# Sheet1.net
KiCad netlist of a schematic drawn in Altium Designer
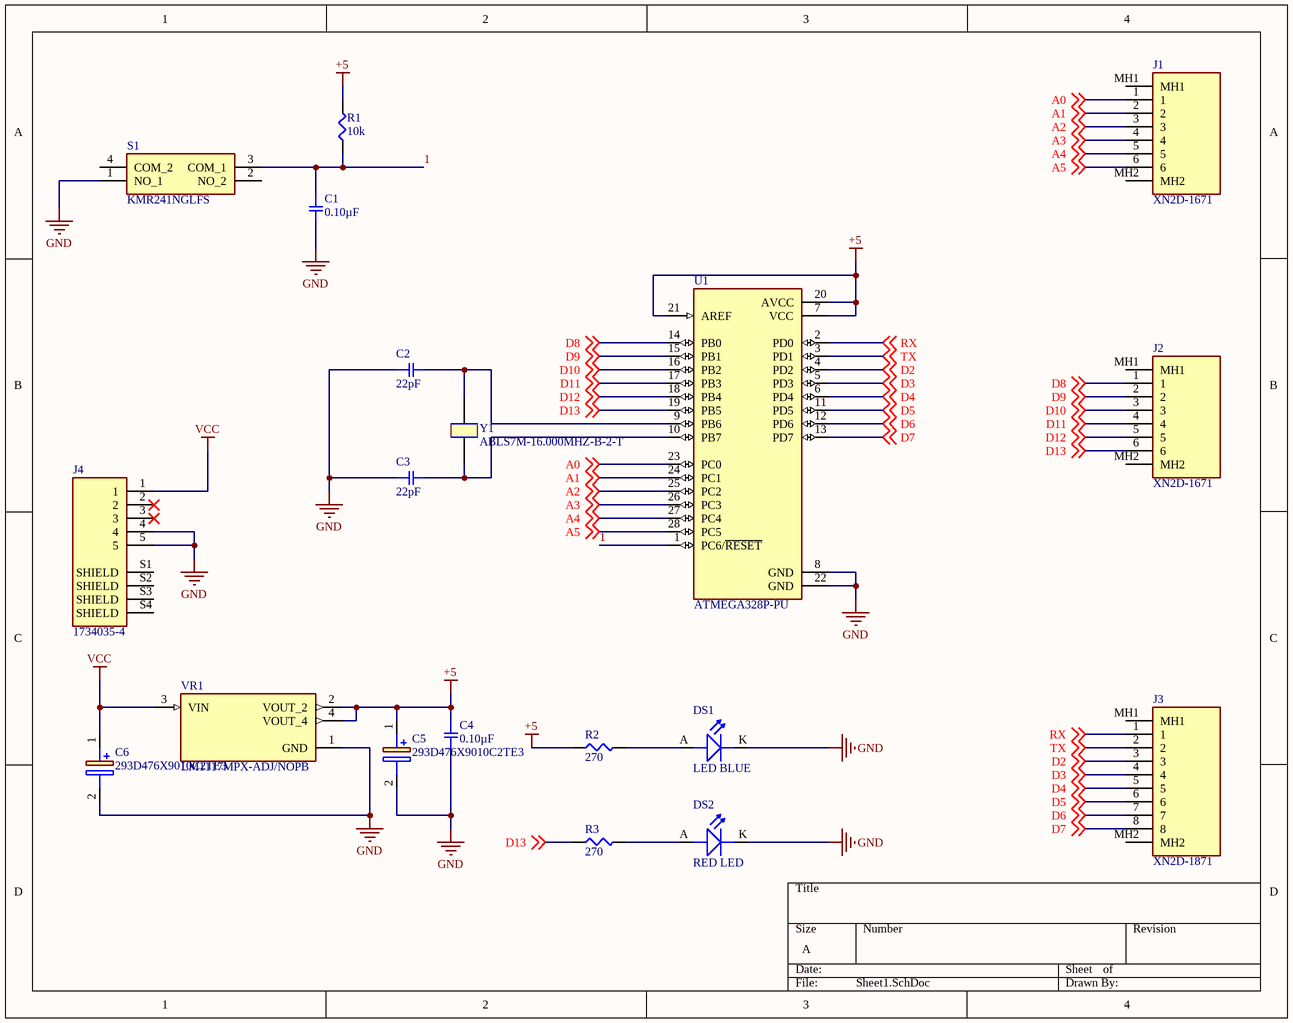
[diagram p0: Sheet1.SchDoc]

(export (version "E")
  (design (tool "Eeschema 10.0.6"))
  (components
    (comp (ref "C1")
      (value "0.10µF")
      (footprint "SMD-0402C")
      (description "CAP CER 0.1UF 16V X7R 0402")
      (fields
        (field (name "DIGI-KEY PART NUMBER") "490-4759-1-ND")
        (field (name "PART NUMBER") "GCM155R71C104KA55D")
      )
      (libsource (lib "capacitor_murata_0402") (part "GCM155R71C104KA55D"))
    )
    (comp (ref "C2")
      (value "22pF")
      (footprint "SMD-0402C")
      (description "CAP CER 22PF 25V NP0 0402")
      (fields
        (field (name "DIGI-KEY PART NUMBER") "490-8173-1-ND")
        (field (name "PART NUMBER") "GRM1555C1E220GA01D")
      )
      (libsource (lib "capacitor_murata_0402") (part "GRM1555C1E220GA01D"))
    )
    (comp (ref "C3")
      (value "22pF")
      (footprint "SMD-0402C")
      (description "CAP CER 22PF 25V NP0 0402")
      (fields
        (field (name "DIGI-KEY PART NUMBER") "490-8173-1-ND")
        (field (name "PART NUMBER") "GRM1555C1E220GA01D")
      )
      (libsource (lib "capacitor_murata_0402") (part "GRM1555C1E220GA01D"))
    )
    (comp (ref "C4")
      (value "0.10µF")
      (footprint "SMD-0402C")
      (description "CAP CER 0.1UF 16V X7R 0402")
      (fields
        (field (name "DIGI-KEY PART NUMBER") "490-4759-1-ND")
        (field (name "PART NUMBER") "GCM155R71C104KA55D")
      )
      (libsource (lib "capacitor_murata_0402") (part "GCM155R71C104KA55D"))
    )
    (comp (ref "C5")
      (value "293D476X9010C2TE3")
      (footprint "SamacSys:CAPPM6032X280N")
      (description "Capacitor Polarised")
      (fields (field (name "MOUSER PART NUMBER") "74-293D476X9010C2TE3"))
      (libsource (lib "*") (part "293D476X9010C2TE3"))
    )
    (comp (ref "C6")
      (value "293D476X9010C2TE3")
      (footprint "SamacSys:CAPPM6032X280N")
      (description "Capacitor Polarised")
      (fields (field (name "MOUSER PART NUMBER") "74-293D476X9010C2TE3"))
      (libsource (lib "*") (part "293D476X9010C2TE3"))
    )
    (comp (ref "DS1")
      (value "LED BLUE")
      (footprint "LED_0805")
      (description "Blue 470nm LED Indication - Discrete 3.3V 0805 (2012 Metric)")
      (fields
        (field (name "MANUFACTURER") "Vishay Lite-On")
        (field (name "MANUFACTURER PART NUMBER") "LTST-C171TBKT")
      )
      (libsource (lib "ESTEEMPCBLIB") (part "LED_BLUE-3V3-20mA-0805"))
    )
    (comp (ref "DS2")
      (value "RED LED")
      (footprint "LED_0805")
      (description "Red 631nm LED Indication - Discrete 2V 0805 (2012 Metric)")
      (fields
        (field (name "MANUFACTURER") "Vishay Lite-On")
        (field (name "MANUFACTURER PART NUMBER") "LTST-C171KRKT")
      )
      (libsource (lib "ESTEEMPCBLIB") (part "LED_RED-2V-20mA-0805"))
    )
    (comp (ref "J1")
      (value "XN2D-1671")
      (footprint "SamacSys:XN2D1671")
      (description "Connector")
      (fields (field (name "MOUSER PART NUMBER") "653-XN2D-1671"))
      (libsource (lib "*") (part "XN2D-1671"))
    )
    (comp (ref "J2")
      (value "XN2D-1671")
      (footprint "SamacSys:XN2D1671")
      (description "Connector")
      (fields (field (name "MOUSER PART NUMBER") "653-XN2D-1671"))
      (libsource (lib "*") (part "XN2D-1671"))
    )
    (comp (ref "J3")
      (value "XN2D-1871")
      (footprint "SamacSys:XN2D1871")
      (description "Connector")
      (libsource (lib "*") (part "XN2D-1871"))
    )
    (comp (ref "J4")
      (value "1734035-4")
      (footprint "1734035-4:J_SMD_1734035-4-5_0.8_9.9_8.85_3.9")
      (description "Conn Mini USB 2.0 Type B RCP 5 POS 0.8mm Solder RA SMD 5 Terminal 1 Port Automotive T/R")
      (fields (field (name "MF") "{'manufacturer': u'TE Connectivity'}"))
      (libsource (lib "*") (part "1734035-4"))
    )
    (comp (ref "R1")
      (value "10k")
      (footprint "SMD-0402-RES")
      (description "RES SMD 10K OHM 5% 1/10W 0402")
      (fields (field (name "PART NUMBER") "ERJ-2GEJ103X") (field (name "DIGI-KEY PART NUMBER") "P10KJCT-ND"))
      (libsource (lib "Panasonic_ERJ_0402") (part "ERJ-2GEJ103X"))
    )
    (comp (ref "R2")
      (value "270")
      (footprint "SMD-0402-RES")
      (description "RES SMD 270 OHM 1% 1/10W 0402")
      (fields (field (name "PART NUMBER") "ERJ-2RKF2700X") (field (name "DIGI-KEY PART NUMBER") "P270LCT-ND"))
      (libsource (lib "Panasonic_ERJ_0402") (part "ERJ-2RKF2700X"))
    )
    (comp (ref "R3")
      (value "270")
      (footprint "SMD-0402-RES")
      (description "RES SMD 270 OHM 1% 1/10W 0402")
      (fields (field (name "PART NUMBER") "ERJ-2RKF2700X") (field (name "DIGI-KEY PART NUMBER") "P270LCT-ND"))
      (libsource (lib "Panasonic_ERJ_0402") (part "ERJ-2RKF2700X"))
    )
    (comp (ref "S1")
      (value "KMR241NGLFS")
      (footprint "SamacSys:KMR241NGLFS")
      (description "Switch")
      (fields (field (name "MOUSER PART NUMBER") "611-KMR241NGLFS"))
      (libsource (lib "SamacSys") (part "KMR241NGLFS"))
    )
    (comp (ref "U1")
      (value "ATMEGA328P-PU")
      (footprint "ATMEGA328P-PU:DIP794W46P254L2967H457Q28B")
      (description "ATmega Series 20 MHz 32 KB Flash 2 KB SRAM 8-Bit Microcontroller - DIP-28")
      (fields (field (name "MF") "{'manufacturer': u'Microchip Technology'}"))
      (libsource (lib "*") (part "ATMEGA328P-PU"))
    )
    (comp (ref "VR1")
      (value "LM1117MPX-ADJ/NOPB")
      (footprint "LM1117MPX-ADJ_NOPB:VREG_LM1117MPX-ADJ/NOPB")
      (fields (field (name "MF") "{'manufacturer': u'Texas Instruments'}"))
      (libsource (lib "*") (part "LM1117MPX-ADJ/NOPB"))
    )
    (comp (ref "Y1")
      (value "ABLS7M-16.000MHZ-B-2-T")
      (footprint "XTAL_314_240X47_SMD")
      (description "16MHz ±20ppm Crystal 18pF 60 Ohms 2-SMD, Flat Lead")
      (fields (field (name "MANUFACTURER") "Abracon"))
      (libsource (lib "ESTEEMPCBLIB") (part "XTAL_16MHz-ABLS7M-16.000MHZ-B-2-T"))
    )
  )
  (nets
    (net (code "1") (name "+5") (class "Default")
      (node (ref "C4") (pin "1") (pinfunction "1_1") (pintype "passive"))
      (node (ref "C5") (pin "1") (pinfunction "+_1") (pintype "passive"))
      (node (ref "R1") (pin "2") (pinfunction "2_2") (pintype "passive"))
      (node (ref "R2") (pin "1") (pinfunction "1_1") (pintype "passive"))
      (node (ref "U1") (pin "20") (pinfunction "AVCC_20") (pintype "power_in"))
      (node (ref "U1") (pin "21") (pinfunction "AREF_21") (pintype "input"))
      (node (ref "U1") (pin "7") (pinfunction "VCC_7") (pintype "power_in"))
      (node (ref "VR1") (pin "2") (pinfunction "VOUT_2_2") (pintype "output"))
      (node (ref "VR1") (pin "4") (pinfunction "VOUT_4_4") (pintype "output"))
    )
    (net (code "2") (name "/1") (class "Default")
      (node (ref "C1") (pin "1") (pinfunction "1_1") (pintype "passive"))
      (node (ref "R1") (pin "1") (pinfunction "1_1") (pintype "passive"))
      (node (ref "S1") (pin "3") (pinfunction "COM_1_3") (pintype "passive"))
      (node (ref "U1") (pin "1") (pinfunction "PC6/~{RESET}_1") (pintype "bidirectional"))
    )
    (net (code "3") (name "A0") (class "Default")
      (node (ref "J1") (pin "1") (pinfunction "1_1") (pintype "passive"))
      (node (ref "U1") (pin "23") (pinfunction "PC0_23") (pintype "bidirectional"))
    )
    (net (code "4") (name "A1") (class "Default")
      (node (ref "J1") (pin "2") (pinfunction "2_2") (pintype "passive"))
      (node (ref "U1") (pin "24") (pinfunction "PC1_24") (pintype "bidirectional"))
    )
    (net (code "5") (name "A2") (class "Default")
      (node (ref "J1") (pin "3") (pinfunction "3_3") (pintype "passive"))
      (node (ref "U1") (pin "25") (pinfunction "PC2_25") (pintype "bidirectional"))
    )
    (net (code "6") (name "A3") (class "Default")
      (node (ref "J1") (pin "4") (pinfunction "4_4") (pintype "passive"))
      (node (ref "U1") (pin "26") (pinfunction "PC3_26") (pintype "bidirectional"))
    )
    (net (code "7") (name "A4") (class "Default")
      (node (ref "J1") (pin "5") (pinfunction "5_5") (pintype "passive"))
      (node (ref "U1") (pin "27") (pinfunction "PC4_27") (pintype "bidirectional"))
    )
    (net (code "8") (name "A5") (class "Default")
      (node (ref "J1") (pin "6") (pinfunction "6_6") (pintype "passive"))
      (node (ref "U1") (pin "28") (pinfunction "PC5_28") (pintype "bidirectional"))
    )
    (net (code "9") (name "D2") (class "Default")
      (node (ref "J3") (pin "3") (pinfunction "3_3") (pintype "passive"))
      (node (ref "U1") (pin "4") (pinfunction "PD2_4") (pintype "bidirectional"))
    )
    (net (code "10") (name "D3") (class "Default")
      (node (ref "J3") (pin "4") (pinfunction "4_4") (pintype "passive"))
      (node (ref "U1") (pin "5") (pinfunction "PD3_5") (pintype "bidirectional"))
    )
    (net (code "11") (name "D4") (class "Default")
      (node (ref "J3") (pin "5") (pinfunction "5_5") (pintype "passive"))
      (node (ref "U1") (pin "6") (pinfunction "PD4_6") (pintype "bidirectional"))
    )
    (net (code "12") (name "D5") (class "Default")
      (node (ref "J3") (pin "6") (pinfunction "6_6") (pintype "passive"))
      (node (ref "U1") (pin "11") (pinfunction "PD5_11") (pintype "bidirectional"))
    )
    (net (code "13") (name "D6") (class "Default")
      (node (ref "J3") (pin "7") (pinfunction "7_7") (pintype "passive"))
      (node (ref "U1") (pin "12") (pinfunction "PD6_12") (pintype "bidirectional"))
    )
    (net (code "14") (name "D7") (class "Default")
      (node (ref "J3") (pin "8") (pinfunction "8_8") (pintype "passive"))
      (node (ref "U1") (pin "13") (pinfunction "PD7_13") (pintype "bidirectional"))
    )
    (net (code "15") (name "D8") (class "Default")
      (node (ref "J2") (pin "1") (pinfunction "1_1") (pintype "passive"))
      (node (ref "U1") (pin "14") (pinfunction "PB0_14") (pintype "bidirectional"))
    )
    (net (code "16") (name "D9") (class "Default")
      (node (ref "J2") (pin "2") (pinfunction "2_2") (pintype "passive"))
      (node (ref "U1") (pin "15") (pinfunction "PB1_15") (pintype "bidirectional"))
    )
    (net (code "17") (name "D10") (class "Default")
      (node (ref "J2") (pin "3") (pinfunction "3_3") (pintype "passive"))
      (node (ref "U1") (pin "16") (pinfunction "PB2_16") (pintype "bidirectional"))
    )
    (net (code "18") (name "D11") (class "Default")
      (node (ref "J2") (pin "4") (pinfunction "4_4") (pintype "passive"))
      (node (ref "U1") (pin "17") (pinfunction "PB3_17") (pintype "bidirectional"))
    )
    (net (code "19") (name "D12") (class "Default")
      (node (ref "J2") (pin "5") (pinfunction "5_5") (pintype "passive"))
      (node (ref "U1") (pin "18") (pinfunction "PB4_18") (pintype "bidirectional"))
    )
    (net (code "20") (name "D13") (class "Default")
      (node (ref "J2") (pin "6") (pinfunction "6_6") (pintype "passive"))
      (node (ref "R3") (pin "1") (pinfunction "1_1") (pintype "passive"))
      (node (ref "U1") (pin "19") (pinfunction "PB5_19") (pintype "bidirectional"))
    )
    (net (code "21") (name "GND") (class "Default")
      (node (ref "C1") (pin "2") (pinfunction "2_2") (pintype "passive"))
      (node (ref "C2") (pin "1") (pinfunction "1_1") (pintype "passive"))
      (node (ref "C3") (pin "1") (pinfunction "1_1") (pintype "passive"))
      (node (ref "C4") (pin "2") (pinfunction "2_2") (pintype "passive"))
      (node (ref "C5") (pin "2") (pinfunction "-_2") (pintype "passive"))
      (node (ref "C6") (pin "2") (pinfunction "-_2") (pintype "passive"))
      (node (ref "DS1") (pin "K") (pinfunction "CATHODE_K") (pintype "passive"))
      (node (ref "DS2") (pin "K") (pinfunction "CATHODE_K") (pintype "passive"))
      (node (ref "J4") (pin "4") (pinfunction "4_4") (pintype "passive"))
      (node (ref "J4") (pin "5") (pinfunction "5_5") (pintype "passive"))
      (node (ref "S1") (pin "1") (pinfunction "NO_1_1") (pintype "passive"))
      (node (ref "U1") (pin "22") (pinfunction "GND_22") (pintype "power_in"))
      (node (ref "U1") (pin "8") (pinfunction "GND_8") (pintype "power_in"))
      (node (ref "VR1") (pin "1") (pinfunction "GND_1") (pintype "power_in"))
    )
    (net (code "22") (name "Net-(DS1-ANODE)") (class "Default")
      (node (ref "DS1") (pin "A") (pinfunction "ANODE_A") (pintype "passive"))
      (node (ref "R2") (pin "2") (pinfunction "2_2") (pintype "passive"))
    )
    (net (code "23") (name "Net-(DS2-ANODE)") (class "Default")
      (node (ref "DS2") (pin "A") (pinfunction "ANODE_A") (pintype "passive"))
      (node (ref "R3") (pin "2") (pinfunction "2_2") (pintype "passive"))
    )
    (net (code "24") (name "Net-(U1-PB6)") (class "Default")
      (node (ref "C2") (pin "2") (pinfunction "2_2") (pintype "passive"))
      (node (ref "U1") (pin "9") (pinfunction "PB6_9") (pintype "bidirectional"))
      (node (ref "Y1") (pin "2") (pinfunction "2_2") (pintype "passive"))
    )
    (net (code "25") (name "Net-(U1-PB7)") (class "Default")
      (node (ref "C3") (pin "2") (pinfunction "2_2") (pintype "passive"))
      (node (ref "U1") (pin "10") (pinfunction "PB7_10") (pintype "bidirectional"))
      (node (ref "Y1") (pin "1") (pinfunction "1_1") (pintype "passive"))
    )
    (net (code "26") (name "RX") (class "Default")
      (node (ref "J3") (pin "1") (pinfunction "1_1") (pintype "passive"))
      (node (ref "U1") (pin "2") (pinfunction "PD0_2") (pintype "bidirectional"))
    )
    (net (code "27") (name "TX") (class "Default")
      (node (ref "J3") (pin "2") (pinfunction "2_2") (pintype "passive"))
      (node (ref "U1") (pin "3") (pinfunction "PD1_3") (pintype "bidirectional"))
    )
    (net (code "28") (name "VCC") (class "Default")
      (node (ref "C6") (pin "1") (pinfunction "+_1") (pintype "passive"))
      (node (ref "J4") (pin "1") (pinfunction "1_1") (pintype "passive"))
      (node (ref "VR1") (pin "3") (pinfunction "VIN_3") (pintype "input"))
    )
    (net (code "29") (name "unconnected-(J1-PadMH1)") (class "Default")
      (node (ref "J1") (pin "MH1") (pinfunction "MH1_MH1") (pintype "passive"))
    )
    (net (code "30") (name "unconnected-(J1-PadMH2)") (class "Default")
      (node (ref "J1") (pin "MH2") (pinfunction "MH2_MH2") (pintype "passive"))
    )
    (net (code "31") (name "unconnected-(J2-PadMH1)") (class "Default")
      (node (ref "J2") (pin "MH1") (pinfunction "MH1_MH1") (pintype "passive"))
    )
    (net (code "32") (name "unconnected-(J2-PadMH2)") (class "Default")
      (node (ref "J2") (pin "MH2") (pinfunction "MH2_MH2") (pintype "passive"))
    )
    (net (code "33") (name "unconnected-(J3-PadMH1)") (class "Default")
      (node (ref "J3") (pin "MH1") (pinfunction "MH1_MH1") (pintype "passive"))
    )
    (net (code "34") (name "unconnected-(J3-PadMH2)") (class "Default")
      (node (ref "J3") (pin "MH2") (pinfunction "MH2_MH2") (pintype "passive"))
    )
    (net (code "35") (name "unconnected-(J4-Pad2)") (class "Default")
      (node (ref "J4") (pin "2") (pinfunction "2_2") (pintype "passive+no_connect"))
    )
    (net (code "36") (name "unconnected-(J4-Pad3)") (class "Default")
      (node (ref "J4") (pin "3") (pinfunction "3_3") (pintype "passive+no_connect"))
    )
    (net (code "37") (name "unconnected-(J4-SHIELD-PadS1)") (class "Default")
      (node (ref "J4") (pin "S1") (pinfunction "SHIELD_S1") (pintype "passive"))
    )
    (net (code "38") (name "unconnected-(J4-SHIELD-PadS2)") (class "Default")
      (node (ref "J4") (pin "S2") (pinfunction "SHIELD_S2") (pintype "passive"))
    )
    (net (code "39") (name "unconnected-(J4-SHIELD-PadS3)") (class "Default")
      (node (ref "J4") (pin "S3") (pinfunction "SHIELD_S3") (pintype "passive"))
    )
    (net (code "40") (name "unconnected-(J4-SHIELD-PadS4)") (class "Default")
      (node (ref "J4") (pin "S4") (pinfunction "SHIELD_S4") (pintype "passive"))
    )
    (net (code "41") (name "unconnected-(S1-COM_2-Pad4)") (class "Default")
      (node (ref "S1") (pin "4") (pinfunction "COM_2_4") (pintype "passive"))
    )
    (net (code "42") (name "unconnected-(S1-NO_2-Pad2)") (class "Default")
      (node (ref "S1") (pin "2") (pinfunction "NO_2_2") (pintype "passive"))
    )
  )
)
